# Peripherals.net
KiCad netlist of a schematic drawn in Altium Designer
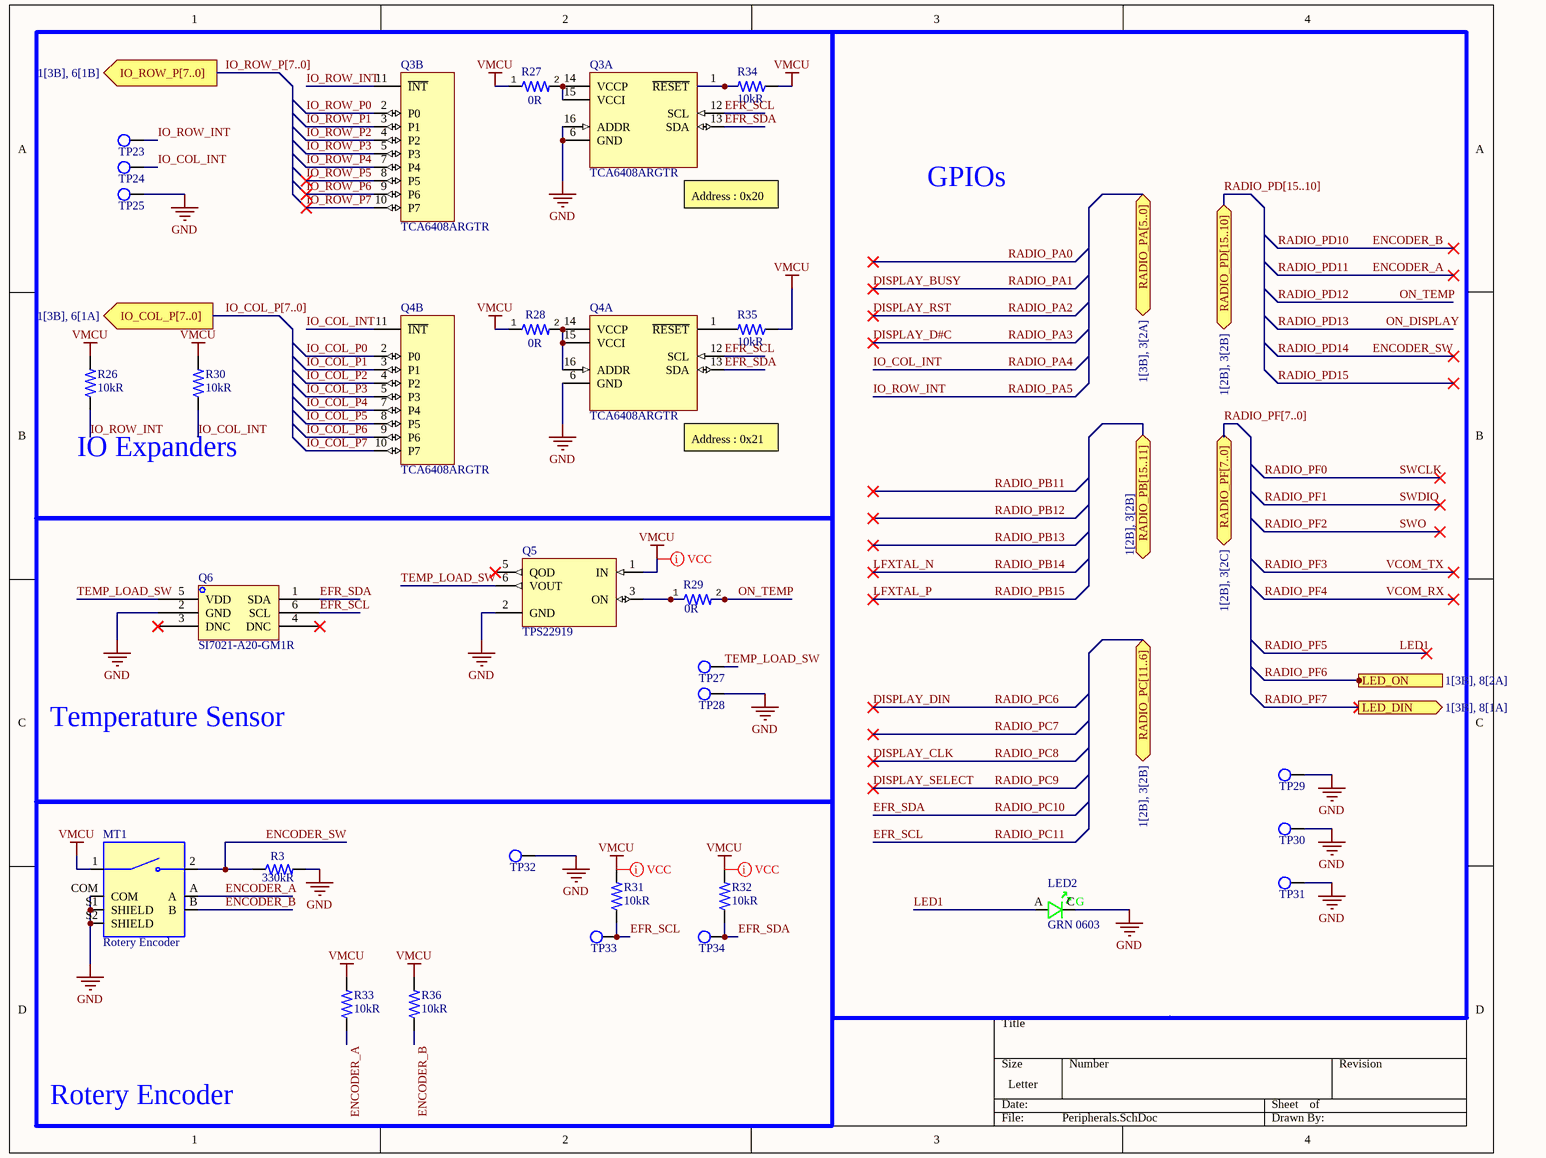
[diagram p0: Peripherals.SchDoc]

(export (version "E")
  (design (tool "Eeschema 10.0.6"))
  (components
    (comp (ref "LED2")
      (value "GRN 0603")
      (footprint "LED 0603")
      (description "LED, 0603, GREEN, 430MCD, 520NM")
      (fields
        (field (name "MANUFACTURER") "Wurth Electronics")
        (field (name "MANUFACTURER PART NUMBER") "150060GS75000")
      )
      (libsource (lib "InsaneIntegratedLib") (part "LED Green 0603"))
    )
    (comp (ref "MT1")
      (value "Rotery Encoder")
      (footprint "Rotery Encoder")
      (description "Rotary Position Encoder, Single, 2 Channels")
      (fields (field (name "MP") "PEC11R-4215F-S0024") (field (name "MANUFACTURER") "Bourns"))
      (libsource (lib "InsaneIntegratedLib") (part "Rotery Encoder"))
    )
    (comp (ref "Q3")
      (value "TCA6408ARGTR")
      (footprint "TCA6408ARGTR - IO Expander")
      (description "Parallel I/O Port, 8-Bit, 8 I/O, CMOS, PQCC16")
      (fields (field (name "MANUFACTURER") "Texas Instruments"))
      (libsource (lib "Keyboard_parts") (part "TCA6408ARGTR"))
    )
    (comp (ref "Q4")
      (value "TCA6408ARGTR")
      (footprint "TCA6408ARGTR - IO Expander")
      (description "Parallel I/O Port, 8-Bit, 8 I/O, CMOS, PQCC16")
      (fields (field (name "MANUFACTURER") "Texas Instruments"))
      (libsource (lib "Keyboard_parts") (part "TCA6408ARGTR"))
    )
    (comp (ref "Q5")
      (value "TPS22919")
      (footprint "TPS22919DCKR - Load SW")
      (description "Buffer/Inverter Based Peripheral Driver, 3A, PDSO6")
      (fields
        (field (name "MANUFACTURER") "Texas Instruments")
        (field (name "MANUFACTURER PART NUMBER") "TPS22919DCKT")
      )
      (libsource (lib "Keyboard_parts") (part "TPS22919"))
    )
    (comp (ref "Q6")
      (value "SI7021-A20-GM1R")
      (footprint "Si7021-A20 - Temp")
      (description "Serial Switch/Digital Sensor, 14 Bit(s), 0.40Cel, Square, Surface Mount")
      (fields (field (name "MANUFACTURER") "Silicon Labs"))
      (libsource (lib "Keyboard_parts") (part "SI7021-A20-GM1R"))
    )
    (comp (ref "R3")
      (value "330kR")
      (footprint "Resistor 0603")
      (fields
        (field (name "MANUFACTURER") "Yageo")
        (field (name "MANUFACTURER PART NUMBER") "RC0603JR-07330KL")
        (field (name "TOLERANCE") "5%")
      )
      (libsource (lib "Keyboard_parts") (part "RES 330K 0603"))
    )
    (comp (ref "R26")
      (value "10kR")
      (footprint "Resistor 0603")
      (fields
        (field (name "MANUFACTURER") "Yageo")
        (field (name "MANUFACTURER PART NUMBER") "RC0603FR-0710KL")
        (field (name "TOLERANCE") "1%")
      )
      (libsource (lib "Keyboard_parts") (part "RES 10K 0603"))
    )
    (comp (ref "R27")
      (value "0R")
      (footprint "Resistor 0402")
      (description "Metal Glaze/thick Film, 0.0625W, 0ohm, Surface Mount, 0402")
      (fields
        (field (name "MANUFACTURER") "Yageo")
        (field (name "MANUFACTURER PART NUMBER") "RC0402JR-070RL")
      )
      (libsource (lib "InsaneIntegratedLib") (part "RES 0R 0402"))
    )
    (comp (ref "R28")
      (value "0R")
      (footprint "Resistor 0402")
      (description "Metal Glaze/thick Film, 0.0625W, 0ohm, Surface Mount, 0402")
      (fields
        (field (name "MANUFACTURER") "Yageo")
        (field (name "MANUFACTURER PART NUMBER") "RC0402JR-070RL")
      )
      (libsource (lib "InsaneIntegratedLib") (part "RES 0R 0402"))
    )
    (comp (ref "R29")
      (value "0R")
      (footprint "Resistor 0402")
      (description "Metal Glaze/thick Film, 0.0625W, 0ohm, Surface Mount, 0402")
      (fields
        (field (name "MANUFACTURER") "Yageo")
        (field (name "MANUFACTURER PART NUMBER") "RC0402JR-070RL")
      )
      (libsource (lib "InsaneIntegratedLib") (part "RES 0R 0402"))
    )
    (comp (ref "R30")
      (value "10kR")
      (footprint "Resistor 0603")
      (fields
        (field (name "MANUFACTURER") "Yageo")
        (field (name "MANUFACTURER PART NUMBER") "RC0603FR-0710KL")
        (field (name "TOLERANCE") "1%")
      )
      (libsource (lib "Keyboard_parts") (part "RES 10K 0603"))
    )
    (comp (ref "R31")
      (value "10kR")
      (footprint "Resistor 0603")
      (fields
        (field (name "MANUFACTURER") "Yageo")
        (field (name "MANUFACTURER PART NUMBER") "RC0603FR-0710KL")
        (field (name "TOLERANCE") "1%")
      )
      (libsource (lib "Keyboard_parts") (part "RES 10K 0603"))
    )
    (comp (ref "R32")
      (value "10kR")
      (footprint "Resistor 0603")
      (fields
        (field (name "MANUFACTURER") "Yageo")
        (field (name "MANUFACTURER PART NUMBER") "RC0603FR-0710KL")
        (field (name "TOLERANCE") "1%")
      )
      (libsource (lib "Keyboard_parts") (part "RES 10K 0603"))
    )
    (comp (ref "R33")
      (value "10kR")
      (footprint "Resistor 0603")
      (fields
        (field (name "MANUFACTURER") "Yageo")
        (field (name "MANUFACTURER PART NUMBER") "RC0603FR-0710KL")
        (field (name "TOLERANCE") "1%")
      )
      (libsource (lib "Keyboard_parts") (part "RES 10K 0603"))
    )
    (comp (ref "R34")
      (value "10kR")
      (footprint "Resistor 0603")
      (fields
        (field (name "MANUFACTURER") "Yageo")
        (field (name "MANUFACTURER PART NUMBER") "RC0603FR-0710KL")
        (field (name "TOLERANCE") "1%")
      )
      (libsource (lib "Keyboard_parts") (part "RES 10K 0603"))
    )
    (comp (ref "R35")
      (value "10kR")
      (footprint "Resistor 0603")
      (fields
        (field (name "MANUFACTURER") "Yageo")
        (field (name "MANUFACTURER PART NUMBER") "RC0603FR-0710KL")
        (field (name "TOLERANCE") "1%")
      )
      (libsource (lib "Keyboard_parts") (part "RES 10K 0603"))
    )
    (comp (ref "R36")
      (value "10kR")
      (footprint "Resistor 0603")
      (fields
        (field (name "MANUFACTURER") "Yageo")
        (field (name "MANUFACTURER PART NUMBER") "RC0603FR-0710KL")
        (field (name "TOLERANCE") "1%")
      )
      (libsource (lib "Keyboard_parts") (part "RES 10K 0603"))
    )
    (comp (ref "TP23")
      (value "Test point")
      (footprint "Test Point")
      (libsource (lib "Keyboard_parts") (part "Test point"))
    )
    (comp (ref "TP24")
      (value "Test point")
      (footprint "Test Point")
      (libsource (lib "Keyboard_parts") (part "Test point"))
    )
    (comp (ref "TP25")
      (value "Test point")
      (footprint "Test Point")
      (libsource (lib "Keyboard_parts") (part "Test point"))
    )
    (comp (ref "TP27")
      (value "Test point")
      (footprint "Test Point")
      (libsource (lib "Keyboard_parts") (part "Test point"))
    )
    (comp (ref "TP28")
      (value "Test point")
      (footprint "Test Point")
      (libsource (lib "Keyboard_parts") (part "Test point"))
    )
    (comp (ref "TP29")
      (value "Test point")
      (footprint "Test Point")
      (libsource (lib "Keyboard_parts") (part "Test point"))
    )
    (comp (ref "TP30")
      (value "Test point")
      (footprint "Test Point")
      (libsource (lib "Keyboard_parts") (part "Test point"))
    )
    (comp (ref "TP31")
      (value "Test point")
      (footprint "Test Point")
      (libsource (lib "Keyboard_parts") (part "Test point"))
    )
    (comp (ref "TP32")
      (value "Test point")
      (footprint "Test Point")
      (libsource (lib "Keyboard_parts") (part "Test point"))
    )
    (comp (ref "TP33")
      (value "Test point")
      (footprint "Test Point")
      (libsource (lib "Keyboard_parts") (part "Test point"))
    )
    (comp (ref "TP34")
      (value "Test point")
      (footprint "Test Point")
      (libsource (lib "Keyboard_parts") (part "Test point"))
    )
  )
  (nets
    (net (code "1") (name "/IO_COL_P0") (class "Default")
      (node (ref "Q4") (pin "2") (pinfunction "P0_2") (pintype "bidirectional"))
    )
    (net (code "2") (name "/IO_COL_P1") (class "Default")
      (node (ref "Q4") (pin "3") (pinfunction "P1_3") (pintype "bidirectional"))
    )
    (net (code "3") (name "/IO_COL_P2") (class "Default")
      (node (ref "Q4") (pin "4") (pinfunction "P2_4") (pintype "bidirectional"))
    )
    (net (code "4") (name "/IO_COL_P3") (class "Default")
      (node (ref "Q4") (pin "5") (pinfunction "P3_5") (pintype "bidirectional"))
    )
    (net (code "5") (name "/IO_COL_P4") (class "Default")
      (node (ref "Q4") (pin "7") (pinfunction "P4_7") (pintype "bidirectional"))
    )
    (net (code "6") (name "/IO_COL_P5") (class "Default")
      (node (ref "Q4") (pin "8") (pinfunction "P5_8") (pintype "bidirectional"))
    )
    (net (code "7") (name "/IO_COL_P6") (class "Default")
      (node (ref "Q4") (pin "9") (pinfunction "P6_9") (pintype "bidirectional"))
    )
    (net (code "8") (name "/IO_COL_P7") (class "Default")
      (node (ref "Q4") (pin "10") (pinfunction "P7_10") (pintype "bidirectional"))
    )
    (net (code "10") (name "/IO_ROW_P0") (class "Default")
      (node (ref "Q3") (pin "2") (pinfunction "P0_2") (pintype "bidirectional"))
    )
    (net (code "11") (name "/IO_ROW_P1") (class "Default")
      (node (ref "Q3") (pin "3") (pinfunction "P1_3") (pintype "bidirectional"))
    )
    (net (code "12") (name "/IO_ROW_P2") (class "Default")
      (node (ref "Q3") (pin "4") (pinfunction "P2_4") (pintype "bidirectional"))
    )
    (net (code "13") (name "/IO_ROW_P3") (class "Default")
      (node (ref "Q3") (pin "5") (pinfunction "P3_5") (pintype "bidirectional"))
    )
    (net (code "14") (name "/IO_ROW_P4") (class "Default")
      (node (ref "Q3") (pin "7") (pinfunction "P4_7") (pintype "bidirectional"))
    )
    (net (code "15") (name "/IO_ROW_P5") (class "Default")
      (node (ref "Q3") (pin "8") (pinfunction "P5_8") (pintype "bidirectional+no_connect"))
    )
    (net (code "16") (name "/IO_ROW_P6") (class "Default")
      (node (ref "Q3") (pin "9") (pinfunction "P6_9") (pintype "bidirectional+no_connect"))
    )
    (net (code "17") (name "/IO_ROW_P7") (class "Default")
      (node (ref "Q3") (pin "10") (pinfunction "P7_10") (pintype "bidirectional+no_connect"))
    )
    (net (code "23") (name "/RADIO_PA4") (class "Default")
      (node (ref "Q4") (pin "11") (pinfunction "~{INT}_11") (pintype "passive"))
      (node (ref "R30") (pin "1") (pinfunction "1_1") (pintype "passive"))
      (node (ref "TP24") (pin "1") (pinfunction "1_1") (pintype "passive"))
    )
    (net (code "24") (name "/RADIO_PA5") (class "Default")
      (node (ref "Q3") (pin "11") (pinfunction "~{INT}_11") (pintype "passive"))
      (node (ref "R26") (pin "1") (pinfunction "1_1") (pintype "passive"))
      (node (ref "TP23") (pin "1") (pinfunction "1_1") (pintype "passive"))
    )
    (net (code "36") (name "/RADIO_PC10") (class "Default")
      (node (ref "Q3") (pin "13") (pinfunction "SDA_13") (pintype "bidirectional"))
      (node (ref "Q4") (pin "13") (pinfunction "SDA_13") (pintype "bidirectional"))
      (node (ref "Q6") (pin "1") (pinfunction "SDA_1") (pintype "passive"))
      (node (ref "R32") (pin "1") (pinfunction "1_1") (pintype "passive"))
      (node (ref "TP34") (pin "1") (pinfunction "1_1") (pintype "passive"))
    )
    (net (code "37") (name "/RADIO_PC11") (class "Default")
      (node (ref "Q3") (pin "12") (pinfunction "SCL_12") (pintype "input"))
      (node (ref "Q4") (pin "12") (pinfunction "SCL_12") (pintype "input"))
      (node (ref "Q6") (pin "6") (pinfunction "SCL_6") (pintype "passive"))
      (node (ref "R31") (pin "1") (pinfunction "1_1") (pintype "passive"))
      (node (ref "TP33") (pin "1") (pinfunction "1_1") (pintype "passive"))
    )
    (net (code "39") (name "/RADIO_PD10") (class "Default")
      (node (ref "MT1") (pin "B") (pinfunction "B_B") (pintype "passive"))
      (node (ref "R36") (pin "1") (pinfunction "1_1") (pintype "passive"))
    )
    (net (code "40") (name "/RADIO_PD11") (class "Default")
      (node (ref "MT1") (pin "A") (pinfunction "A_A") (pintype "passive"))
      (node (ref "R33") (pin "1") (pinfunction "1_1") (pintype "passive"))
    )
    (net (code "41") (name "/RADIO_PD12") (class "Default")
      (node (ref "R29") (pin "2") (pinfunction "2_2") (pintype "passive"))
    )
    (net (code "43") (name "/RADIO_PD14") (class "Default")
      (node (ref "MT1") (pin "2") (pinfunction "2_2") (pintype "passive"))
      (node (ref "R3") (pin "1") (pinfunction "1_1") (pintype "passive"))
    )
    (net (code "51") (name "/RADIO_PF5") (class "Default")
      (node (ref "LED2") (pin "A") (pinfunction "A_A") (pintype "passive"))
    )
    (net (code "55") (name "/TEMP_LOAD_SW") (class "Default")
      (node (ref "Q5") (pin "6") (pinfunction "VOUT_6") (pintype "output"))
      (node (ref "Q6") (pin "5") (pinfunction "VDD_5") (pintype "passive"))
      (node (ref "TP27") (pin "1") (pinfunction "1_1") (pintype "passive"))
    )
    (net (code "56") (name "GND") (class "Default")
      (node (ref "LED2") (pin "C") (pinfunction "C_C") (pintype "passive"))
      (node (ref "MT1") (pin "COM") (pinfunction "COM_COM") (pintype "passive"))
      (node (ref "MT1") (pin "S1") (pinfunction "SHIELD_S1") (pintype "passive"))
      (node (ref "MT1") (pin "S2") (pinfunction "SHIELD_S2") (pintype "passive"))
      (node (ref "Q3") (pin "16") (pinfunction "ADDR_16") (pintype "input"))
      (node (ref "Q3") (pin "6") (pinfunction "GND_6") (pintype "passive"))
      (node (ref "Q4") (pin "6") (pinfunction "GND_6") (pintype "passive"))
      (node (ref "Q5") (pin "2") (pinfunction "GND_2") (pintype "passive"))
      (node (ref "Q6") (pin "2") (pinfunction "GND_2") (pintype "passive"))
      (node (ref "R3") (pin "2") (pinfunction "2_2") (pintype "passive"))
      (node (ref "TP25") (pin "1") (pinfunction "1_1") (pintype "passive"))
      (node (ref "TP28") (pin "1") (pinfunction "1_1") (pintype "passive"))
      (node (ref "TP29") (pin "1") (pinfunction "1_1") (pintype "passive"))
      (node (ref "TP30") (pin "1") (pinfunction "1_1") (pintype "passive"))
      (node (ref "TP31") (pin "1") (pinfunction "1_1") (pintype "passive"))
      (node (ref "TP32") (pin "1") (pinfunction "1_1") (pintype "passive"))
    )
    (net (code "57") (name "Net-(Q3A-VCCI)") (class "Default")
      (node (ref "Q3") (pin "14") (pinfunction "VCCP_14") (pintype "power_in"))
      (node (ref "Q3") (pin "15") (pinfunction "VCCI_15") (pintype "power_in"))
      (node (ref "R27") (pin "2") (pinfunction "2_2") (pintype "passive"))
    )
    (net (code "58") (name "Net-(Q3A-~{RESET})") (class "Default")
      (node (ref "Q3") (pin "1") (pinfunction "~{RESET}_1") (pintype "passive"))
      (node (ref "R34") (pin "2") (pinfunction "2_2") (pintype "passive"))
    )
    (net (code "59") (name "Net-(Q4A-ADDR)") (class "Default")
      (node (ref "Q4") (pin "14") (pinfunction "VCCP_14") (pintype "power_in"))
      (node (ref "Q4") (pin "15") (pinfunction "VCCI_15") (pintype "power_in"))
      (node (ref "Q4") (pin "16") (pinfunction "ADDR_16") (pintype "input"))
      (node (ref "R28") (pin "2") (pinfunction "2_2") (pintype "passive"))
    )
    (net (code "60") (name "Net-(Q4A-~{RESET})") (class "Default")
      (node (ref "Q4") (pin "1") (pinfunction "~{RESET}_1") (pintype "passive"))
      (node (ref "R35") (pin "2") (pinfunction "2_2") (pintype "passive"))
    )
    (net (code "61") (name "Net-(Q5-ON)") (class "Default")
      (node (ref "Q5") (pin "3") (pinfunction "ON_3") (pintype "bidirectional"))
      (node (ref "R29") (pin "1") (pinfunction "1_1") (pintype "passive"))
    )
    (net (code "62") (name "VMCU") (class "Default")
      (node (ref "MT1") (pin "1") (pinfunction "1_1") (pintype "passive"))
      (node (ref "Q5") (pin "1") (pinfunction "IN_1") (pintype "input"))
      (node (ref "R26") (pin "2") (pinfunction "2_2") (pintype "passive"))
      (node (ref "R27") (pin "1") (pinfunction "1_1") (pintype "passive"))
      (node (ref "R28") (pin "1") (pinfunction "1_1") (pintype "passive"))
      (node (ref "R30") (pin "2") (pinfunction "2_2") (pintype "passive"))
      (node (ref "R31") (pin "2") (pinfunction "2_2") (pintype "passive"))
      (node (ref "R32") (pin "2") (pinfunction "2_2") (pintype "passive"))
      (node (ref "R33") (pin "2") (pinfunction "2_2") (pintype "passive"))
      (node (ref "R34") (pin "1") (pinfunction "1_1") (pintype "passive"))
      (node (ref "R35") (pin "1") (pinfunction "1_1") (pintype "passive"))
      (node (ref "R36") (pin "2") (pinfunction "2_2") (pintype "passive"))
    )
    (net (code "63") (name "unconnected-(Q5-QOD-Pad5)") (class "Default")
      (node (ref "Q5") (pin "5") (pinfunction "QOD_5") (pintype "output+no_connect"))
    )
    (net (code "64") (name "unconnected-(Q6-DNC-Pad3)") (class "Default")
      (node (ref "Q6") (pin "3") (pinfunction "DNC_3") (pintype "passive+no_connect"))
    )
    (net (code "65") (name "unconnected-(Q6-DNC-Pad4)") (class "Default")
      (node (ref "Q6") (pin "4") (pinfunction "DNC_4") (pintype "passive+no_connect"))
    )
  )
)
